# mic-input.net
KiCad netlist of a schematic drawn in EAGLE
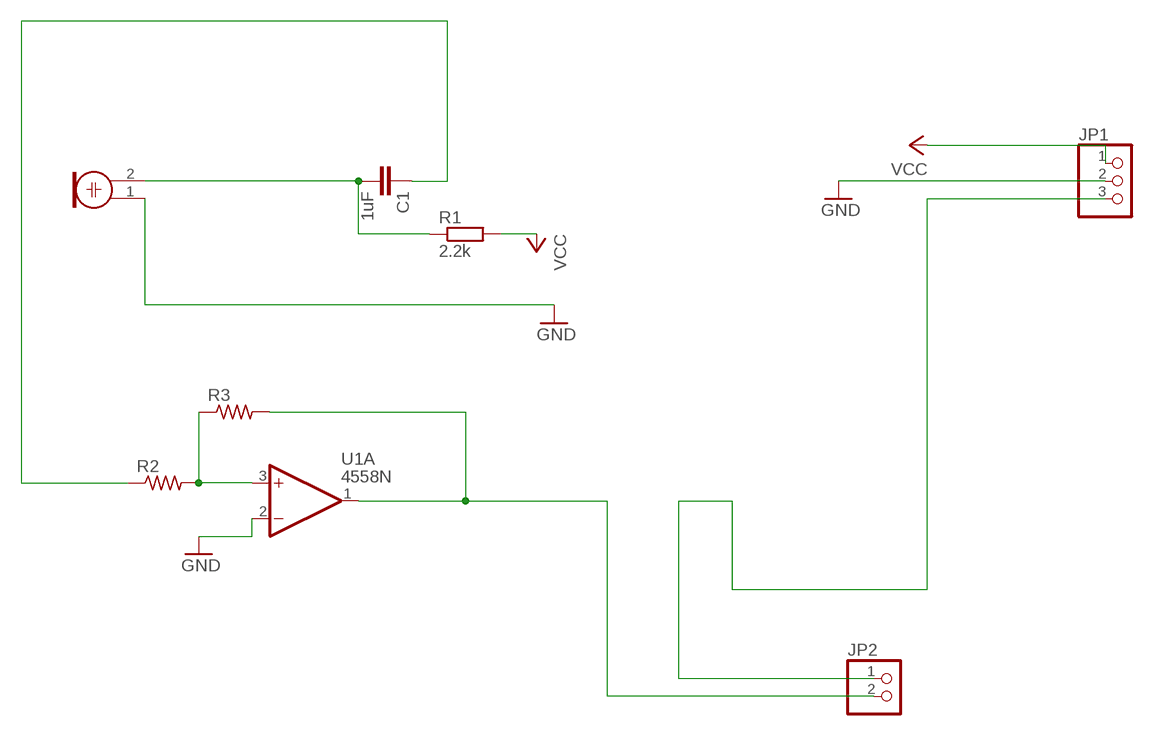
[diagram p0: schematic, sheet 1]

(export (version "E")
  (design (tool "Eeschema 10.0.6"))
  (components
    (comp (ref "C1")
      (value "1uF")
      (footprint "eagle-import:C2.5-3")
      (libsource (lib "eagle-import") (part "C2,5-3"))
    )
    (comp (ref "JP1")
      (value "PINHD-1X3")
      (footprint "eagle-import:1X03")
      (libsource (lib "eagle-import") (part "PINHD-1X3"))
    )
    (comp (ref "JP2")
      (value "PINHD-1X2")
      (footprint "eagle-import:1X02")
      (libsource (lib "eagle-import") (part "PINHD-1X2"))
    )
    (comp (ref "M1")
      (value "ELECTRET_MICROPHON-F6050AP")
      (footprint "eagle-import:F6050AP")
      (libsource (lib "eagle-import") (part "ELECTRET_MICROPHON-F6050AP"))
    )
    (comp (ref "R1")
      (value "2.2k")
      (footprint "eagle-import:0204_7")
      (libsource (lib "eagle-import") (part "R-EU_0204/7"))
    )
    (comp (ref "R2")
      (value "R-US_0204/7")
      (footprint "eagle-import:0204_7")
      (libsource (lib "eagle-import") (part "R-US_0204/7"))
    )
    (comp (ref "R3")
      (value "R-US_0204/7")
      (footprint "eagle-import:0204_7")
      (libsource (lib "eagle-import") (part "R-US_0204/7"))
    )
    (comp (ref "U1")
      (value "4558N")
      (footprint "eagle-import:DIL08")
      (libsource (lib "eagle-import") (part "4558N"))
    )
  )
  (nets
    (net (code "1") (name "GND") (class "Default")
      (node (ref "JP1") (pin "2") (pinfunction "2_2") (pintype "passive"))
      (node (ref "M1") (pin "1") (pinfunction "1_1") (pintype "passive"))
      (node (ref "U1") (pin "2") (pinfunction "-IN_2") (pintype "input"))
    )
    (net (code "2") (name "Net-(C1-Pad1)") (class "Default")
      (node (ref "C1") (pin "1") (pinfunction "1_1") (pintype "passive"))
      (node (ref "R2") (pin "1") (pinfunction "1_1") (pintype "passive"))
    )
    (net (code "3") (name "Net-(C1-Pad2)") (class "Default")
      (node (ref "C1") (pin "2") (pinfunction "2_2") (pintype "passive"))
      (node (ref "M1") (pin "2") (pinfunction "2_2") (pintype "passive"))
      (node (ref "R1") (pin "1") (pinfunction "1_1") (pintype "passive"))
    )
    (net (code "4") (name "Net-(JP1-Pad3)") (class "Default")
      (node (ref "JP1") (pin "3") (pinfunction "3_3") (pintype "passive"))
      (node (ref "JP2") (pin "1") (pinfunction "1_1") (pintype "passive"))
    )
    (net (code "5") (name "Net-(U1A-+IN)") (class "Default")
      (node (ref "R2") (pin "2") (pinfunction "2_2") (pintype "passive"))
      (node (ref "R3") (pin "1") (pinfunction "1_1") (pintype "passive"))
      (node (ref "U1") (pin "3") (pinfunction "+IN_3") (pintype "input"))
    )
    (net (code "6") (name "Net-(U1A-OUT)") (class "Default")
      (node (ref "JP2") (pin "2") (pinfunction "2_2") (pintype "passive"))
      (node (ref "R3") (pin "2") (pinfunction "2_2") (pintype "passive"))
      (node (ref "U1") (pin "1") (pinfunction "OUT_1") (pintype "output"))
    )
    (net (code "7") (name "VCC") (class "Default")
      (node (ref "JP1") (pin "1") (pinfunction "1_1") (pintype "passive"))
      (node (ref "R1") (pin "2") (pinfunction "2_2") (pintype "passive"))
    )
  )
)
